# SAMV71_Xplained_Ultra_Power_Multiplexer.net
KiCad netlist of a schematic drawn in Altium Designer
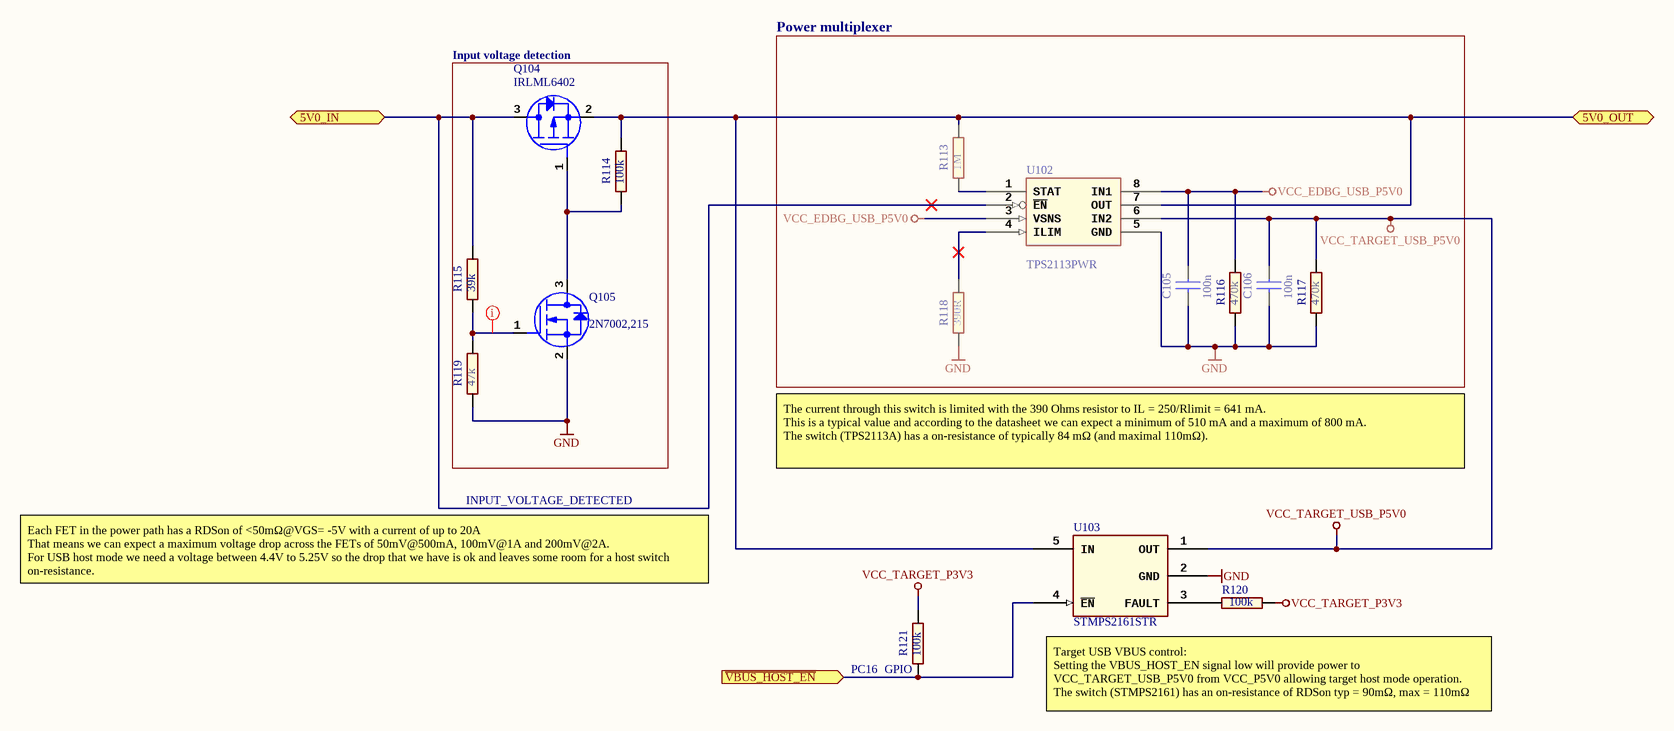
[diagram p0: SAMV71_Xplained_Ultra_Power_Multiplexer.SchDoc]

(export (version "E")
  (design (tool "Eeschema 10.0.6"))
  (components
    (comp (ref "C105")
      (value "100n")
      (footprint "AP1-00001")
      (description "Ceramic capacitor, SMD 0402, X7R, 16V, +/-10%")
      (fields (field (name "TOLERANCE") "16V, +/-10%") (field (name "MANUFACTURER") "Kemet"))
      (libsource (lib "AltiumDbLib") (part "CAP-NONPOL"))
    )
    (comp (ref "C106")
      (value "100n")
      (footprint "AP1-00001")
      (description "Ceramic capacitor, SMD 0402, X7R, 16V, +/-10%")
      (fields (field (name "TOLERANCE") "16V, +/-10%") (field (name "MANUFACTURER") "Kemet"))
      (libsource (lib "AltiumDbLib") (part "CAP-NONPOL"))
    )
    (comp (ref "Q104")
      (value "IRLML6402")
      (footprint "AP5-00002")
      (description "P-ch. MOSFET. -30V, -3.7A continuous,RDS(ON)=0.05Ohm@VGS=-4,5V, RDS(ON)=0.08Ohm@VGS=-2.5V")
      (fields (field (name "MANUFACTURER") "International Rectifier") (field (name "MPN") "IRLML6402PBF"))
      (libsource (lib "AltiumDbLib") (part "MOSFET_P_GSD"))
    )
    (comp (ref "Q105")
      (value "2N7002,215")
      (footprint "AP5-00002")
      (description "N-Channel MOSFET. 60V, 0.300A continuous, 1.2A Peak. RDS(ON) = 3.8Ohm@VGS=4.5V, VGS(th)<2.5V")
      (fields (field (name "MANUFACTURER") "NXP"))
      (libsource (lib "AltiumDbLib") (part "MOSFET_N_GSD"))
    )
    (comp (ref "R113")
      (value "1M")
      (footprint "AP2-00000")
      (description "Thick film resistor, SMD 0402, 1/16W, 1%")
      (fields (field (name "TOLERANCE") "1 %") (field (name "MANUFACTURER") "ASJ"))
      (libsource (lib "") (part "R2_1"))
    )
    (comp (ref "R114")
      (value "100k")
      (footprint "AP2-00000")
      (description "Thick film resistor, SMD 0402, 1/16W, 1%")
      (fields (field (name "TOLERANCE") "1 %") (field (name "MANUFACTURER") "ASJ"))
      (libsource (lib "") (part "R2_1"))
    )
    (comp (ref "R115")
      (value "39k")
      (footprint "AP2-00000")
      (description "Thick film resistor, SMD 0402, 1/16W, 1%")
      (fields (field (name "TOLERANCE") "1 %") (field (name "MANUFACTURER") "ASJ"))
      (libsource (lib "") (part "R2_1"))
    )
    (comp (ref "R116")
      (value "470k")
      (footprint "AP2-00000")
      (description "Thick film resistor, SMD 0402, 1/16W, 1%")
      (fields (field (name "TOLERANCE") "1 %") (field (name "MANUFACTURER") "ASJ"))
      (libsource (lib "") (part "R2_1"))
    )
    (comp (ref "R117")
      (value "470k")
      (footprint "AP2-00000")
      (description "Thick film resistor, SMD 0402, 1/16W, 1%")
      (fields (field (name "TOLERANCE") "1 %") (field (name "MANUFACTURER") "ASJ"))
      (libsource (lib "") (part "R2_1"))
    )
    (comp (ref "R118")
      (value "390R")
      (footprint "AP2-00000")
      (description "Thick film resistor, SMD 0402, 1/16W, 1%")
      (fields (field (name "TOLERANCE") "1 %") (field (name "MANUFACTURER") "ASJ"))
      (libsource (lib "") (part "R2_1"))
    )
    (comp (ref "R119")
      (value "47k")
      (footprint "AP2-00000")
      (description "Thick film resistor, SMD 0402, 1/16W, 1%")
      (fields (field (name "TOLERANCE") "1 %") (field (name "MANUFACTURER") "KOA"))
      (libsource (lib "") (part "R2_1"))
    )
    (comp (ref "R120")
      (value "100k")
      (footprint "AP2-00011")
      (description "Thick film resistor, SMD 0402, 1/16W, 1%")
      (fields (field (name "TOLERANCE") "1 %") (field (name "MANUFACTURER") "ASJ"))
      (libsource (lib "AltiumDbLib") (part "R2"))
    )
    (comp (ref "R121")
      (value "100k")
      (footprint "AP2-00011")
      (description "Thick film resistor, SMD 0402, 1/16W, 1%")
      (fields (field (name "TOLERANCE") "1 %") (field (name "MANUFACTURER") "ASJ"))
      (libsource (lib "") (part "R2_1"))
    )
    (comp (ref "U102")
      (value "TPS2113PWR")
      (footprint "AP6-00054")
      (description "Autoswitching 2:1 Power Mux")
      (fields (field (name "MANUFACTURER") "Texas Instruments"))
      (libsource (lib "AltiumDbLib") (part "TPS2112"))
    )
    (comp (ref "U103")
      (value "STMPS2161STR")
      (footprint "AP6-00087")
      (description "Single channel power switch, 1A, reverse block, active low enabled.")
      (fields (field (name "TOLERANCE") "2.7 to 5.5V") (field (name "MANUFACTURER") "ST"))
      (libsource (lib "AltiumDbLib") (part "STMPS2161"))
    )
  )
  (nets
    (net (code "1") (name "/5V0_IN") (class "Default")
      (node (ref "Q104") (pin "3") (pinfunction "D_3") (pintype "passive"))
      (node (ref "R115") (pin "2") (pinfunction "2_2") (pintype "passive"))
      (node (ref "U102") (pin "2") (pinfunction "~{EN}_2") (pintype "input"))
    )
    (net (code "2") (name "/5V0_OUT") (class "Default")
      (node (ref "Q104") (pin "2") (pinfunction "S_2") (pintype "passive"))
      (node (ref "R113") (pin "2") (pinfunction "2_2") (pintype "passive"))
      (node (ref "R114") (pin "2") (pinfunction "2_2") (pintype "passive"))
      (node (ref "U102") (pin "7") (pinfunction "OUT_7") (pintype "power_in"))
      (node (ref "U103") (pin "5") (pinfunction "IN_5") (pintype "power_in"))
    )
    (net (code "3") (name "/~{VBUS_HOST_EN}") (class "Default")
      (node (ref "R121") (pin "1") (pinfunction "1_1") (pintype "passive"))
      (node (ref "U103") (pin "4") (pinfunction "~{EN}_4") (pintype "input"))
    )
    (net (code "4") (name "GND") (class "Default")
      (node (ref "C105") (pin "2") (pinfunction "2_2") (pintype "passive"))
      (node (ref "C106") (pin "2") (pinfunction "2_2") (pintype "passive"))
      (node (ref "Q105") (pin "2") (pinfunction "S_2") (pintype "passive"))
      (node (ref "R116") (pin "1") (pinfunction "1_1") (pintype "passive"))
      (node (ref "R117") (pin "1") (pinfunction "1_1") (pintype "passive"))
      (node (ref "R118") (pin "1") (pinfunction "1_1") (pintype "passive"))
      (node (ref "R119") (pin "1") (pinfunction "1_1") (pintype "passive"))
      (node (ref "U102") (pin "5") (pinfunction "GND_5") (pintype "power_in"))
      (node (ref "U103") (pin "2") (pinfunction "GND_2") (pintype "power_in"))
    )
    (net (code "5") (name "Net-(Q104-G)") (class "Default")
      (node (ref "Q104") (pin "1") (pinfunction "G_1") (pintype "passive"))
      (node (ref "Q105") (pin "3") (pinfunction "D_3") (pintype "passive"))
      (node (ref "R114") (pin "1") (pinfunction "1_1") (pintype "passive"))
    )
    (net (code "6") (name "Net-(Q105-G)") (class "Default")
      (node (ref "Q105") (pin "1") (pinfunction "G_1") (pintype "passive"))
      (node (ref "R115") (pin "1") (pinfunction "1_1") (pintype "passive"))
      (node (ref "R119") (pin "2") (pinfunction "2_2") (pintype "passive"))
    )
    (net (code "7") (name "Net-(U102-ILIM)") (class "Default")
      (node (ref "R118") (pin "2") (pinfunction "2_2") (pintype "passive"))
      (node (ref "U102") (pin "4") (pinfunction "ILIM_4") (pintype "input"))
    )
    (net (code "8") (name "Net-(U102-STAT)") (class "Default")
      (node (ref "R113") (pin "1") (pinfunction "1_1") (pintype "passive"))
      (node (ref "U102") (pin "1") (pinfunction "STAT_1") (pintype "open_collector"))
    )
    (net (code "9") (name "Net-(U103-FAULT)") (class "Default")
      (node (ref "R120") (pin "2") (pinfunction "2_2") (pintype "passive"))
      (node (ref "U103") (pin "3") (pinfunction "FAULT_3") (pintype "open_collector"))
    )
    (net (code "10") (name "VCC_EDBG_USB_P5V0") (class "Default")
      (node (ref "C105") (pin "1") (pinfunction "1_1") (pintype "passive"))
      (node (ref "R116") (pin "2") (pinfunction "2_2") (pintype "passive"))
      (node (ref "U102") (pin "3") (pinfunction "VSNS_3") (pintype "input"))
      (node (ref "U102") (pin "8") (pinfunction "IN1_8") (pintype "power_in"))
    )
    (net (code "11") (name "VCC_TARGET_P3V3") (class "Default")
      (node (ref "R120") (pin "1") (pinfunction "1_1") (pintype "passive"))
      (node (ref "R121") (pin "2") (pinfunction "2_2") (pintype "passive"))
    )
    (net (code "12") (name "VCC_TARGET_USB_P5V0") (class "Default")
      (node (ref "C106") (pin "1") (pinfunction "1_1") (pintype "passive"))
      (node (ref "R117") (pin "2") (pinfunction "2_2") (pintype "passive"))
      (node (ref "U102") (pin "6") (pinfunction "IN2_6") (pintype "power_in"))
      (node (ref "U103") (pin "1") (pinfunction "OUT_1") (pintype "power_in"))
    )
  )
)
